# Dev.net
KiCad netlist of a schematic drawn in Altium Designer
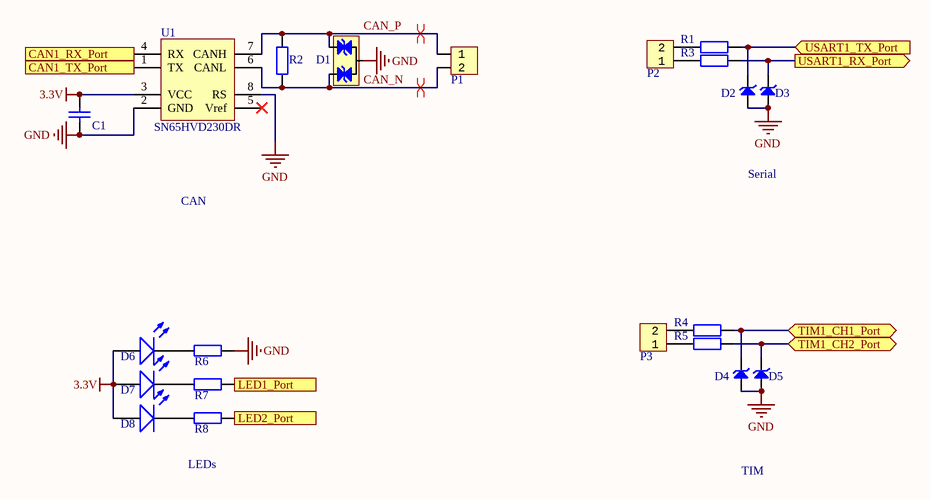
[diagram p0: Dev.SchDoc]

(export (version "E")
  (design (tool "Eeschema 10.0.6"))
  (components
    (comp (ref "C1")
      (value "100nF")
      (footprint "CAP-0603")
      (description "贴片电容")
      (libsource (lib "Power_Lib_Altium") (part "CAP"))
    )
    (comp (ref "D1")
      (value "PESD2CAN")
      (footprint "SOT-23-3")
      (description "TVS 双向x2")
      (libsource (lib "Power_Lib_Altium") (part "TVS_C2"))
    )
    (comp (ref "D2")
      (value "BZT52C3V9S-7-F")
      (footprint "SOD_323")
      (description "TVS 二极管")
      (libsource (lib "Power_Lib_Altium") (part "TVS"))
    )
    (comp (ref "D3")
      (value "BZT52C3V9S-7-F")
      (footprint "SOD_323")
      (description "TVS 二极管")
      (libsource (lib "Power_Lib_Altium") (part "TVS"))
    )
    (comp (ref "D4")
      (value "BZT52C3V9S-7-F")
      (footprint "SOD_323")
      (description "TVS 二极管")
      (libsource (lib "Power_Lib_Altium") (part "TVS"))
    )
    (comp (ref "D5")
      (value "BZT52C3V9S-7-F")
      (footprint "SOD_323")
      (description "TVS 二极管")
      (libsource (lib "Power_Lib_Altium") (part "TVS"))
    )
    (comp (ref "D6")
      (value "RED")
      (footprint "LED_0603")
      (description "发光二极管")
      (libsource (lib "Power_Lib_Altium") (part "LED"))
    )
    (comp (ref "D7")
      (value "RED")
      (footprint "LED_0603")
      (description "发光二极管")
      (libsource (lib "Power_Lib_Altium") (part "LED"))
    )
    (comp (ref "D8")
      (value "GREEN")
      (footprint "LED_0603")
      (description "发光二极管")
      (libsource (lib "Power_Lib_Altium") (part "LED"))
    )
    (comp (ref "P1")
      (value "HDR1x2_2.54")
      (footprint "HDR1X2_2.54_180")
      (description "Header")
      (libsource (lib "Power_Lib_Altium") (part "HDR1x2_2.54"))
    )
    (comp (ref "P2")
      (value "HDR1x2_2.54")
      (footprint "HDR1X2_2.54_180")
      (description "Header")
      (libsource (lib "") (part "HDR1x2_2.54_1"))
    )
    (comp (ref "P3")
      (value "HDR1x2_2.54")
      (footprint "HDR1X2_2.54_180")
      (description "Header")
      (libsource (lib "") (part "HDR1x2_2.54_1"))
    )
    (comp (ref "R1")
      (value "100R")
      (footprint "R-0603")
      (description "贴片电阻")
      (libsource (lib "Power_Lib_Altium") (part "RES"))
    )
    (comp (ref "R2")
      (value "120R")
      (footprint "R-0603")
      (description "贴片电阻")
      (libsource (lib "") (part "RES_1"))
    )
    (comp (ref "R3")
      (value "100R")
      (footprint "R-0603")
      (description "贴片电阻")
      (libsource (lib "Power_Lib_Altium") (part "RES"))
    )
    (comp (ref "R4")
      (value "100R")
      (footprint "R-0603")
      (description "贴片电阻")
      (libsource (lib "Power_Lib_Altium") (part "RES"))
    )
    (comp (ref "R5")
      (value "100R")
      (footprint "R-0603")
      (description "贴片电阻")
      (libsource (lib "Power_Lib_Altium") (part "RES"))
    )
    (comp (ref "R6")
      (value "4.7K")
      (footprint "R-0603")
      (description "贴片电阻")
      (libsource (lib "Power_Lib_Altium") (part "RES"))
    )
    (comp (ref "R7")
      (value "4.7K")
      (footprint "R-0603")
      (description "贴片电阻")
      (libsource (lib "Power_Lib_Altium") (part "RES"))
    )
    (comp (ref "R8")
      (value "4.7K")
      (footprint "R-0603")
      (description "贴片电阻")
      (libsource (lib "Power_Lib_Altium") (part "RES"))
    )
    (comp (ref "U1")
      (value "SN65HVD230DR")
      (footprint "SOIC_8")
      (description "CAN 控制器（3.3V）")
      (libsource (lib "Power_Lib_Altium") (part "SN65HVD230DR"))
    )
  )
  (nets
    (net (code "1") (name "/CAN1_RX_Port") (class "Default")
      (node (ref "U1") (pin "4") (pinfunction "RX_4") (pintype "passive"))
    )
    (net (code "2") (name "/CAN1_TX_Port") (class "Default")
      (node (ref "U1") (pin "1") (pinfunction "TX_1") (pintype "passive"))
    )
    (net (code "3") (name "/CAN_N") (class "Default")
      (node (ref "D1") (pin "1") (pinfunction "1_1") (pintype "passive"))
      (node (ref "P1") (pin "2") (pinfunction "2_2") (pintype "passive"))
      (node (ref "R2") (pin "1") (pinfunction "1_1") (pintype "passive"))
      (node (ref "U1") (pin "6") (pinfunction "CANL_6") (pintype "passive"))
    )
    (net (code "4") (name "/CAN_P") (class "Default")
      (node (ref "D1") (pin "2") (pinfunction "2_2") (pintype "passive"))
      (node (ref "P1") (pin "1") (pinfunction "1_1") (pintype "passive"))
      (node (ref "R2") (pin "2") (pinfunction "2_2") (pintype "passive"))
      (node (ref "U1") (pin "7") (pinfunction "CANH_7") (pintype "passive"))
    )
    (net (code "5") (name "/LED1_Port") (class "Default")
      (node (ref "R7") (pin "2") (pinfunction "2_2") (pintype "passive"))
    )
    (net (code "6") (name "/LED2_Port") (class "Default")
      (node (ref "R8") (pin "2") (pinfunction "2_2") (pintype "passive"))
    )
    (net (code "7") (name "/TIM1_CH1_Port") (class "Default")
      (node (ref "D4") (pin "2") (pinfunction "2_2") (pintype "passive"))
      (node (ref "R4") (pin "2") (pinfunction "2_2") (pintype "passive"))
    )
    (net (code "8") (name "/TIM1_CH2_Port") (class "Default")
      (node (ref "D5") (pin "2") (pinfunction "2_2") (pintype "passive"))
      (node (ref "R5") (pin "2") (pinfunction "2_2") (pintype "passive"))
    )
    (net (code "9") (name "/USART1_RX_Port") (class "Default")
      (node (ref "D3") (pin "2") (pinfunction "2_2") (pintype "passive"))
      (node (ref "R3") (pin "2") (pinfunction "2_2") (pintype "passive"))
    )
    (net (code "10") (name "/USART1_TX_Port") (class "Default")
      (node (ref "D2") (pin "2") (pinfunction "2_2") (pintype "passive"))
      (node (ref "R1") (pin "2") (pinfunction "2_2") (pintype "passive"))
    )
    (net (code "11") (name "3.3V") (class "Default")
      (node (ref "C1") (pin "2") (pinfunction "2_2") (pintype "passive"))
      (node (ref "D6") (pin "A") (pinfunction "A_A") (pintype "passive"))
      (node (ref "D7") (pin "A") (pinfunction "A_A") (pintype "passive"))
      (node (ref "D8") (pin "A") (pinfunction "A_A") (pintype "passive"))
      (node (ref "U1") (pin "3") (pinfunction "VCC_3") (pintype "passive"))
    )
    (net (code "12") (name "GND") (class "Default")
      (node (ref "C1") (pin "1") (pinfunction "1_1") (pintype "passive"))
      (node (ref "D1") (pin "3") (pinfunction "3_3") (pintype "passive"))
      (node (ref "D2") (pin "1") (pinfunction "1_1") (pintype "passive"))
      (node (ref "D3") (pin "1") (pinfunction "1_1") (pintype "passive"))
      (node (ref "D4") (pin "1") (pinfunction "1_1") (pintype "passive"))
      (node (ref "D5") (pin "1") (pinfunction "1_1") (pintype "passive"))
      (node (ref "R6") (pin "2") (pinfunction "2_2") (pintype "passive"))
      (node (ref "U1") (pin "2") (pinfunction "GND_2") (pintype "passive"))
      (node (ref "U1") (pin "8") (pinfunction "RS_8") (pintype "passive"))
    )
    (net (code "13") (name "Net-(D6-PadK)") (class "Default")
      (node (ref "D6") (pin "K") (pinfunction "K_K") (pintype "passive"))
      (node (ref "R6") (pin "1") (pinfunction "1_1") (pintype "passive"))
    )
    (net (code "14") (name "Net-(D7-PadK)") (class "Default")
      (node (ref "D7") (pin "K") (pinfunction "K_K") (pintype "passive"))
      (node (ref "R7") (pin "1") (pinfunction "1_1") (pintype "passive"))
    )
    (net (code "15") (name "Net-(D8-PadK)") (class "Default")
      (node (ref "D8") (pin "K") (pinfunction "K_K") (pintype "passive"))
      (node (ref "R8") (pin "1") (pinfunction "1_1") (pintype "passive"))
    )
    (net (code "16") (name "Net-(P2-Pad1)") (class "Default")
      (node (ref "P2") (pin "1") (pinfunction "1_1") (pintype "passive"))
      (node (ref "R3") (pin "1") (pinfunction "1_1") (pintype "passive"))
    )
    (net (code "17") (name "Net-(P2-Pad2)") (class "Default")
      (node (ref "P2") (pin "2") (pinfunction "2_2") (pintype "passive"))
      (node (ref "R1") (pin "1") (pinfunction "1_1") (pintype "passive"))
    )
    (net (code "18") (name "Net-(P3-Pad1)") (class "Default")
      (node (ref "P3") (pin "1") (pinfunction "1_1") (pintype "passive"))
      (node (ref "R5") (pin "1") (pinfunction "1_1") (pintype "passive"))
    )
    (net (code "19") (name "Net-(P3-Pad2)") (class "Default")
      (node (ref "P3") (pin "2") (pinfunction "2_2") (pintype "passive"))
      (node (ref "R4") (pin "1") (pinfunction "1_1") (pintype "passive"))
    )
    (net (code "20") (name "unconnected-(U1-Vref-Pad5)") (class "Default")
      (node (ref "U1") (pin "5") (pinfunction "Vref_5") (pintype "passive+no_connect"))
    )
  )
)
